# Sheet_1_copy_copy_copy_2022-03-16.net
KiCad netlist of a schematic drawn in Altium Designer
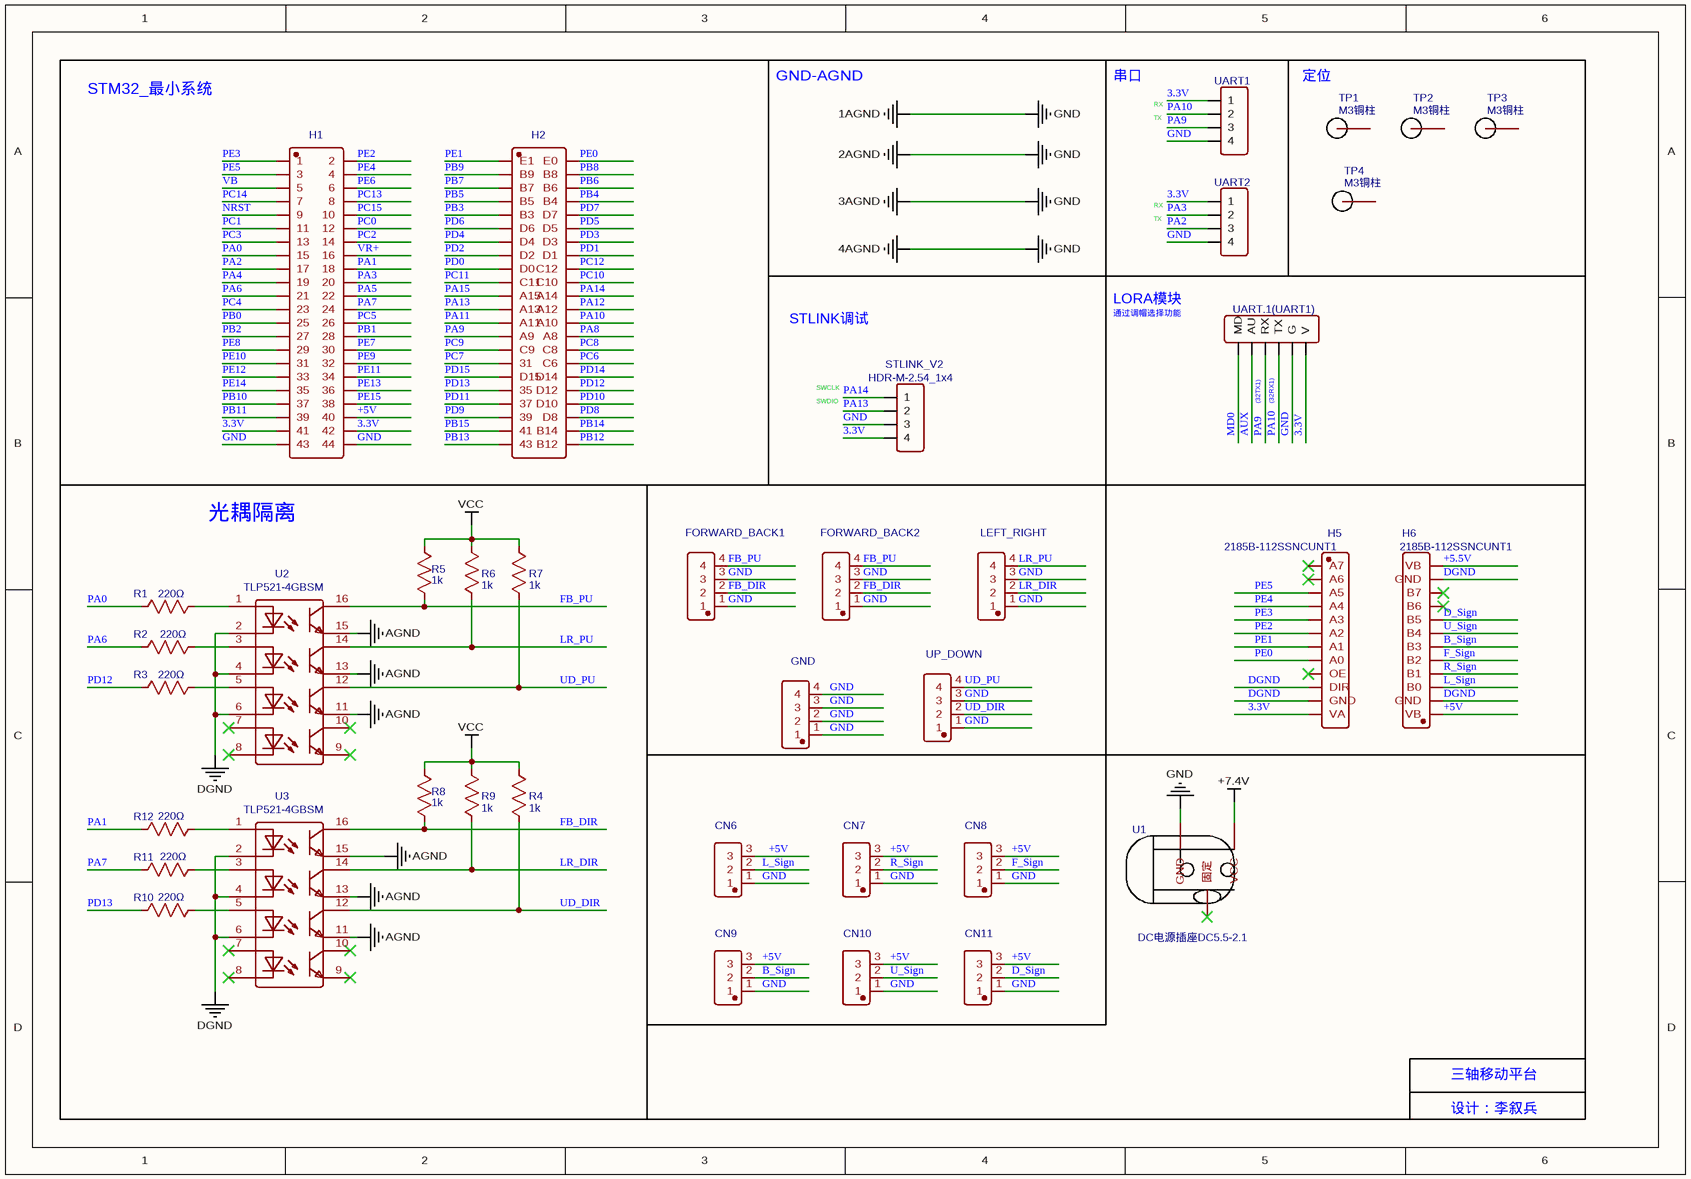
[diagram p0: Sheet_1 copy copy copy_2022-03-16.schdoc]

(export (version "E")
  (design (tool "Eeschema 10.0.6"))
  (components
    (comp (ref "CN6")
      (value "15ETYRC-3.81-03P-14-00AH")
      (footprint "CONN-TH_15ETYRC-3.81-03P-14-00AH")
      (fields (field (name "BOM_SUPPLIER PART") "C2828333") (field (name "CONTRIBUTOR") "LCSC"))
      (libsource (lib "altium-import") (part "root_2_15ETYRC-3.81-03P-14-00AH_"))
    )
    (comp (ref "CN7")
      (value "15ETYRC-3.81-03P-14-00AH")
      (footprint "CONN-TH_15ETYRC-3.81-03P-14-00AH")
      (fields (field (name "BOM_SUPPLIER PART") "C2828333") (field (name "CONTRIBUTOR") "LCSC"))
      (libsource (lib "altium-import") (part "root_2_15ETYRC-3.81-03P-14-00AH_"))
    )
    (comp (ref "CN8")
      (value "15ETYRC-3.81-03P-14-00AH")
      (footprint "CONN-TH_15ETYRC-3.81-03P-14-00AH")
      (fields (field (name "BOM_SUPPLIER PART") "C2828333") (field (name "CONTRIBUTOR") "LCSC"))
      (libsource (lib "altium-import") (part "root_2_15ETYRC-3.81-03P-14-00AH_"))
    )
    (comp (ref "CN9")
      (value "15ETYRC-3.81-03P-14-00AH")
      (footprint "CONN-TH_15ETYRC-3.81-03P-14-00AH")
      (fields (field (name "BOM_SUPPLIER PART") "C2828333") (field (name "CONTRIBUTOR") "LCSC"))
      (libsource (lib "altium-import") (part "root_2_15ETYRC-3.81-03P-14-00AH_"))
    )
    (comp (ref "CN10")
      (value "15ETYRC-3.81-03P-14-00AH")
      (footprint "CONN-TH_15ETYRC-3.81-03P-14-00AH")
      (fields (field (name "BOM_SUPPLIER PART") "C2828333") (field (name "CONTRIBUTOR") "LCSC"))
      (libsource (lib "altium-import") (part "root_2_15ETYRC-3.81-03P-14-00AH_"))
    )
    (comp (ref "CN11")
      (value "15ETYRC-3.81-03P-14-00AH")
      (footprint "CONN-TH_15ETYRC-3.81-03P-14-00AH")
      (fields (field (name "BOM_SUPPLIER PART") "C2828333") (field (name "CONTRIBUTOR") "LCSC"))
      (libsource (lib "altium-import") (part "root_2_15ETYRC-3.81-03P-14-00AH_"))
    )
    (comp (ref "FORWARD_BACK1")
      (value "15ETYRC-3.81-04P-14-00AH")
      (footprint "CONN-TH_15ETYRC-3.81-04P-14-00AH")
      (fields (field (name "BOM_SUPPLIER PART") "C2828334") (field (name "CONTRIBUTOR") "LCSC"))
      (libsource (lib "altium-import") (part "root_2_15ETYRC-3.81-04P-14-00AH_"))
    )
    (comp (ref "FORWARD_BACK2")
      (value "15ETYRC-3.81-04P-14-00AH")
      (footprint "CONN-TH_15ETYRC-3.81-04P-14-00AH")
      (fields (field (name "BOM_SUPPLIER PART") "C2828334") (field (name "CONTRIBUTOR") "LCSC"))
      (libsource (lib "altium-import") (part "root_2_15ETYRC-3.81-04P-14-00AH_"))
    )
    (comp (ref "GND")
      (value "15ETYRC-3.81-04P-14-00AH")
      (footprint "CONN-TH_15ETYRC-3.81-04P-14-00AH")
      (fields (field (name "BOM_SUPPLIER PART") "C2828334") (field (name "CONTRIBUTOR") "LCSC"))
      (libsource (lib "altium-import") (part "root_2_15ETYRC-3.81-04P-14-00AH_"))
    )
    (comp (ref "H1")
      (value "X5521FV-2X22C70D30-1000")
      (footprint "HDR-TH_44P-P2.54-V-F-R2-C22-S2.54")
      (fields
        (field (name "BOM_SUPPLIER PART") "C2682209")
        (field (name "BOM_MANUFACTURER PART") "X5521FV-2x22C70D30-1000")
        (field (name "CONTRIBUTOR") "LCSC")
      )
      (libsource (lib "altium-import") (part "root_0_X5521FV-2X22C70D30-1000_"))
    )
    (comp (ref "H2")
      (value "从5")
      (footprint "HDR-TH_44P-P2.54-V-F-R2-C22-S2.54")
      (fields
        (field (name "BOM_SUPPLIER PART") "C2682209")
        (field (name "BOM_MANUFACTURER PART") "X5521FV-2x22C70D30-1000")
        (field (name "CONTRIBUTOR") "LCSC")
      )
      (libsource (lib "altium-import") (part "root_0_从5_"))
    )
    (comp (ref "H5")
      (value "2185B-112SSNCUNT1")
      (footprint "HDR-TH_12P-P2.54-V-F")
      (fields (field (name "BOM_SUPPLIER PART") "C721800") (field (name "CONTRIBUTOR") "LCSC"))
      (libsource (lib "altium-import") (part "root_0_2185B-112SSNCUNT1_"))
    )
    (comp (ref "H6")
      (value "2185B-112SSNCUNT1")
      (footprint "HDR-TH_12P-P2.54-V-F")
      (fields (field (name "BOM_SUPPLIER PART") "C721800") (field (name "CONTRIBUTOR") "LCSC"))
      (libsource (lib "altium-import") (part "root_2_2185B-112SSNCUNT1_"))
    )
    (comp (ref "LEFT_RIGHT")
      (value "15ETYRC-3.81-04P-14-00AH")
      (footprint "CONN-TH_15ETYRC-3.81-04P-14-00AH")
      (fields (field (name "BOM_SUPPLIER PART") "C2828334") (field (name "CONTRIBUTOR") "LCSC"))
      (libsource (lib "altium-import") (part "root_2_15ETYRC-3.81-04P-14-00AH_"))
    )
    (comp (ref "R1")
      (value "220Ω")
      (footprint "R0603")
      (fields (field (name "CONTRIBUTOR") "LCEDA_Lib"))
      (libsource (lib "altium-import") (part "root_0_220Ω_"))
    )
    (comp (ref "R2")
      (value "220Ω")
      (footprint "R0603")
      (fields (field (name "CONTRIBUTOR") "LCEDA_Lib"))
      (libsource (lib "altium-import") (part "root_0_220Ω_"))
    )
    (comp (ref "R3")
      (value "220Ω")
      (footprint "R0603")
      (fields (field (name "CONTRIBUTOR") "LCEDA_Lib"))
      (libsource (lib "altium-import") (part "root_0_220Ω_"))
    )
    (comp (ref "R4")
      (value "1k")
      (footprint "R0603")
      (fields (field (name "CONTRIBUTOR") "LCEDA_Lib"))
      (libsource (lib "altium-import") (part "root_1_1k_"))
    )
    (comp (ref "R5")
      (value "1k")
      (footprint "R0603")
      (fields (field (name "CONTRIBUTOR") "LCEDA_Lib"))
      (libsource (lib "altium-import") (part "root_1_1k_"))
    )
    (comp (ref "R6")
      (value "1k")
      (footprint "R0603")
      (fields (field (name "CONTRIBUTOR") "LCEDA_Lib"))
      (libsource (lib "altium-import") (part "root_3_1k_"))
    )
    (comp (ref "R7")
      (value "1k")
      (footprint "R0603")
      (fields (field (name "CONTRIBUTOR") "LCEDA_Lib"))
      (libsource (lib "altium-import") (part "root_1_1k_"))
    )
    (comp (ref "R8")
      (value "1k")
      (footprint "R0603")
      (fields (field (name "CONTRIBUTOR") "LCEDA_Lib"))
      (libsource (lib "altium-import") (part "root_1_1k_"))
    )
    (comp (ref "R9")
      (value "1k")
      (footprint "R0603")
      (fields (field (name "CONTRIBUTOR") "LCEDA_Lib"))
      (libsource (lib "altium-import") (part "root_3_1k_"))
    )
    (comp (ref "R10")
      (value "220Ω")
      (footprint "R0603")
      (fields (field (name "CONTRIBUTOR") "LCEDA_Lib"))
      (libsource (lib "altium-import") (part "root_0_220Ω_"))
    )
    (comp (ref "R11")
      (value "220Ω")
      (footprint "R0603")
      (fields (field (name "CONTRIBUTOR") "LCEDA_Lib"))
      (libsource (lib "altium-import") (part "root_0_220Ω_"))
    )
    (comp (ref "R12")
      (value "220Ω")
      (footprint "R0603")
      (fields (field (name "CONTRIBUTOR") "LCEDA_Lib"))
      (libsource (lib "altium-import") (part "root_0_220Ω_"))
    )
    (comp (ref "STLINK_V2")
      (value "HDR-M-2.54_1x4")
      (footprint "HDR-M-2.54_1X4")
      (fields (field (name "BOM_SUPPLIER PART") "C124378") (field (name "CONTRIBUTOR") "LCEDA_Lib"))
      (libsource (lib "altium-import") (part "root_0_HDR-M-2.54_1x4_"))
    )
    (comp (ref "TP1")
      (value "M3铜柱")
      (footprint "M3铜柱")
      (fields (field (name "CONTRIBUTOR") "xzxzhao"))
      (libsource (lib "altium-import") (part "root_0_M3铜柱_"))
    )
    (comp (ref "TP2")
      (value "M3铜柱")
      (footprint "M3铜柱")
      (fields (field (name "CONTRIBUTOR") "xzxzhao"))
      (libsource (lib "altium-import") (part "root_0_M3铜柱_"))
    )
    (comp (ref "TP3")
      (value "M3铜柱")
      (footprint "M3铜柱")
      (fields (field (name "CONTRIBUTOR") "xzxzhao"))
      (libsource (lib "altium-import") (part "root_0_M3铜柱_"))
    )
    (comp (ref "TP4")
      (value "M3铜柱")
      (footprint "M3铜柱")
      (fields (field (name "CONTRIBUTOR") "xzxzhao"))
      (libsource (lib "altium-import") (part "root_0_M3铜柱_"))
    )
    (comp (ref "U1")
      (value "DC电源插座DC5.5-2.1")
      (footprint "DC电源插座5.5-2.1")
      (fields (field (name "CONTRIBUTOR") "Ros智能车"))
      (libsource (lib "altium-import") (part "root_0_DC电源插座DC5.5-2.1_"))
    )
    (comp (ref "U2")
      (value "TLP521-4GBSM")
      (footprint "OPTO-SMD-16_L20.0-W6.5-P2.54-LS10.2-BL")
      (fields (field (name "BOM_SUPPLIER PART") "C191332") (field (name "CONTRIBUTOR") "LCSC"))
      (libsource (lib "altium-import") (part "root_0_TLP521-4GBSM_"))
    )
    (comp (ref "U3")
      (value "TLP521-4GBSM")
      (footprint "OPTO-SMD-16_L20.0-W6.5-P2.54-LS10.2-BL")
      (fields (field (name "BOM_SUPPLIER PART") "C191332") (field (name "CONTRIBUTOR") "LCSC"))
      (libsource (lib "altium-import") (part "root_0_TLP521-4GBSM_"))
    )
    (comp (ref "UART.1(UART1)")
      (value "HDR-F-2.54_1x6")
      (footprint "HDR-F-2.54_1X6")
      (fields (field (name "BOM_SUPPLIER PART") "C40877") (field (name "CONTRIBUTOR") "LCEDA_Lib"))
      (libsource (lib "altium-import") (part "root_1_HDR-F-2.54_1x6_"))
    )
    (comp (ref "UART1")
      (value "HDR-M-2.54_1x4")
      (footprint "HDR-M-2.54_1X4")
      (fields (field (name "BOM_SUPPLIER PART") "C124378") (field (name "CONTRIBUTOR") "LCEDA_Lib"))
      (libsource (lib "altium-import") (part "root_0_HDR-M-2.54_1x4_"))
    )
    (comp (ref "UART2")
      (value "HDR-M-2.54_1x4")
      (footprint "HDR-M-2.54_1X4")
      (fields (field (name "BOM_SUPPLIER PART") "C124378") (field (name "CONTRIBUTOR") "LCEDA_Lib"))
      (libsource (lib "altium-import") (part "root_0_HDR-M-2.54_1x4_"))
    )
    (comp (ref "UP_DOWN")
      (value "15ETYRC-3.81-04P-14-00AH")
      (footprint "CONN-TH_15ETYRC-3.81-04P-14-00AH")
      (fields (field (name "BOM_SUPPLIER PART") "C2828334") (field (name "CONTRIBUTOR") "LCSC"))
      (libsource (lib "altium-import") (part "root_2_15ETYRC-3.81-04P-14-00AH_"))
    )
  )
  (nets
    (net (code "1") (name "+7.4V") (class "Default")
      (node (ref "U1") (pin "1") (pinfunction "VCC_1") (pintype "passive"))
    )
    (net (code "2") (name "/+5.5V") (class "Default")
      (node (ref "H6") (pin "12") (pinfunction "VB_12") (pintype "passive"))
    )
    (net (code "3") (name "/+5V") (class "Default")
      (node (ref "CN10") (pin "3") (pinfunction "3_3") (pintype "passive"))
      (node (ref "CN11") (pin "3") (pinfunction "3_3") (pintype "passive"))
      (node (ref "CN6") (pin "3") (pinfunction "3_3") (pintype "passive"))
      (node (ref "CN7") (pin "3") (pinfunction "3_3") (pintype "passive"))
      (node (ref "CN8") (pin "3") (pinfunction "3_3") (pintype "passive"))
      (node (ref "CN9") (pin "3") (pinfunction "3_3") (pintype "passive"))
      (node (ref "H1") (pin "40") (pinfunction "40_40") (pintype "passive"))
      (node (ref "H6") (pin "1") (pinfunction "VB_1") (pintype "passive"))
    )
    (net (code "4") (name "/3.3V") (class "Default")
      (node (ref "H1") (pin "41") (pinfunction "41_41") (pintype "passive"))
      (node (ref "H1") (pin "42") (pinfunction "42_42") (pintype "passive"))
      (node (ref "H5") (pin "12") (pinfunction "VA_12") (pintype "passive"))
      (node (ref "STLINK_V2") (pin "4") (pinfunction "4_4") (pintype "passive"))
      (node (ref "UART.1(UART1)") (pin "6") (pinfunction "V_6") (pintype "passive"))
      (node (ref "UART1") (pin "1") (pinfunction "1_1") (pintype "passive"))
      (node (ref "UART2") (pin "1") (pinfunction "1_1") (pintype "passive"))
    )
    (net (code "5") (name "/AUX") (class "Default")
      (node (ref "UART.1(UART1)") (pin "2") (pinfunction "AU_2") (pintype "passive"))
    )
    (net (code "6") (name "/B_Sign") (class "Default")
      (node (ref "CN9") (pin "2") (pinfunction "2_2") (pintype "passive"))
      (node (ref "H6") (pin "6") (pinfunction "B3_6") (pintype "passive"))
    )
    (net (code "7") (name "/D_Sign") (class "Default")
      (node (ref "CN11") (pin "2") (pinfunction "2_2") (pintype "passive"))
      (node (ref "H6") (pin "8") (pinfunction "B5_8") (pintype "passive"))
    )
    (net (code "8") (name "/FB_DIR") (class "Default")
      (node (ref "FORWARD_BACK1") (pin "2") (pinfunction "2_2") (pintype "passive"))
      (node (ref "FORWARD_BACK2") (pin "2") (pinfunction "2_2") (pintype "passive"))
      (node (ref "R8") (pin "1") (pinfunction "1_1") (pintype "passive"))
      (node (ref "U3") (pin "16") (pinfunction "COL_16") (pintype "passive"))
    )
    (net (code "9") (name "/FB_PU") (class "Default")
      (node (ref "FORWARD_BACK1") (pin "4") (pinfunction "4_4") (pintype "passive"))
      (node (ref "FORWARD_BACK2") (pin "4") (pinfunction "4_4") (pintype "passive"))
      (node (ref "R5") (pin "1") (pinfunction "1_1") (pintype "passive"))
      (node (ref "U2") (pin "16") (pinfunction "COL_16") (pintype "passive"))
    )
    (net (code "10") (name "/F_Sign") (class "Default")
      (node (ref "CN8") (pin "2") (pinfunction "2_2") (pintype "passive"))
      (node (ref "H6") (pin "5") (pinfunction "B2_5") (pintype "passive"))
    )
    (net (code "11") (name "/LR_DIR") (class "Default")
      (node (ref "LEFT_RIGHT") (pin "2") (pinfunction "2_2") (pintype "passive"))
      (node (ref "R9") (pin "2") (pinfunction "2_2") (pintype "passive"))
      (node (ref "U3") (pin "14") (pinfunction "COL_14") (pintype "passive"))
    )
    (net (code "12") (name "/LR_PU") (class "Default")
      (node (ref "LEFT_RIGHT") (pin "4") (pinfunction "4_4") (pintype "passive"))
      (node (ref "R6") (pin "2") (pinfunction "2_2") (pintype "passive"))
      (node (ref "U2") (pin "14") (pinfunction "COL_14") (pintype "passive"))
    )
    (net (code "13") (name "/L_Sign") (class "Default")
      (node (ref "CN6") (pin "2") (pinfunction "2_2") (pintype "passive"))
      (node (ref "H6") (pin "3") (pinfunction "B0_3") (pintype "passive"))
    )
    (net (code "14") (name "/MD0") (class "Default")
      (node (ref "UART.1(UART1)") (pin "1") (pinfunction "MD_1") (pintype "passive"))
    )
    (net (code "15") (name "/NRST") (class "Default")
      (node (ref "H1") (pin "9") (pinfunction "9_9") (pintype "passive"))
    )
    (net (code "16") (name "/PA0") (class "Default")
      (node (ref "H1") (pin "15") (pinfunction "15_15") (pintype "passive"))
      (node (ref "R1") (pin "1") (pinfunction "1_1") (pintype "passive"))
    )
    (net (code "17") (name "/PA1") (class "Default")
      (node (ref "H1") (pin "18") (pinfunction "18_18") (pintype "passive"))
      (node (ref "R12") (pin "1") (pinfunction "1_1") (pintype "passive"))
    )
    (net (code "18") (name "/PA2") (class "Default")
      (node (ref "H1") (pin "17") (pinfunction "17_17") (pintype "passive"))
      (node (ref "UART2") (pin "3") (pinfunction "3_3") (pintype "passive"))
    )
    (net (code "19") (name "/PA3") (class "Default")
      (node (ref "H1") (pin "20") (pinfunction "20_20") (pintype "passive"))
      (node (ref "UART2") (pin "2") (pinfunction "2_2") (pintype "passive"))
    )
    (net (code "20") (name "/PA4") (class "Default")
      (node (ref "H1") (pin "19") (pinfunction "19_19") (pintype "passive"))
    )
    (net (code "21") (name "/PA5") (class "Default")
      (node (ref "H1") (pin "22") (pinfunction "22_22") (pintype "passive"))
    )
    (net (code "22") (name "/PA6") (class "Default")
      (node (ref "H1") (pin "21") (pinfunction "21_21") (pintype "passive"))
      (node (ref "R2") (pin "1") (pinfunction "1_1") (pintype "passive"))
    )
    (net (code "23") (name "/PA7") (class "Default")
      (node (ref "H1") (pin "24") (pinfunction "24_24") (pintype "passive"))
      (node (ref "R11") (pin "1") (pinfunction "1_1") (pintype "passive"))
    )
    (net (code "24") (name "/PA8") (class "Default")
      (node (ref "H2") (pin "28") (pinfunction "A8_28") (pintype "passive"))
    )
    (net (code "25") (name "/PA9") (class "Default")
      (node (ref "H2") (pin "27") (pinfunction "A9_27") (pintype "passive"))
      (node (ref "UART.1(UART1)") (pin "3") (pinfunction "RX_3") (pintype "passive"))
      (node (ref "UART1") (pin "3") (pinfunction "3_3") (pintype "passive"))
    )
    (net (code "26") (name "/PA10") (class "Default")
      (node (ref "H2") (pin "26") (pinfunction "A10_26") (pintype "passive"))
      (node (ref "UART.1(UART1)") (pin "4") (pinfunction "TX_4") (pintype "passive"))
      (node (ref "UART1") (pin "2") (pinfunction "2_2") (pintype "passive"))
    )
    (net (code "27") (name "/PA11") (class "Default")
      (node (ref "H2") (pin "25") (pinfunction "A11_25") (pintype "passive"))
    )
    (net (code "28") (name "/PA12") (class "Default")
      (node (ref "H2") (pin "24") (pinfunction "A12_24") (pintype "passive"))
    )
    (net (code "29") (name "/PA13") (class "Default")
      (node (ref "H2") (pin "23") (pinfunction "A13_23") (pintype "passive"))
      (node (ref "STLINK_V2") (pin "2") (pinfunction "2_2") (pintype "passive"))
    )
    (net (code "30") (name "/PA14") (class "Default")
      (node (ref "H2") (pin "22") (pinfunction "A14_22") (pintype "passive"))
      (node (ref "STLINK_V2") (pin "1") (pinfunction "1_1") (pintype "passive"))
    )
    (net (code "31") (name "/PA15") (class "Default")
      (node (ref "H2") (pin "21") (pinfunction "A15_21") (pintype "passive"))
    )
    (net (code "32") (name "/PB0") (class "Default")
      (node (ref "H1") (pin "25") (pinfunction "25_25") (pintype "passive"))
    )
    (net (code "33") (name "/PB1") (class "Default")
      (node (ref "H1") (pin "28") (pinfunction "28_28") (pintype "passive"))
    )
    (net (code "34") (name "/PB2") (class "Default")
      (node (ref "H1") (pin "27") (pinfunction "27_27") (pintype "passive"))
    )
    (net (code "35") (name "/PB3") (class "Default")
      (node (ref "H2") (pin "9") (pinfunction "B3_9") (pintype "passive"))
    )
    (net (code "36") (name "/PB4") (class "Default")
      (node (ref "H2") (pin "8") (pinfunction "B4_8") (pintype "passive"))
    )
    (net (code "37") (name "/PB5") (class "Default")
      (node (ref "H2") (pin "7") (pinfunction "B5_7") (pintype "passive"))
    )
    (net (code "38") (name "/PB6") (class "Default")
      (node (ref "H2") (pin "6") (pinfunction "B6_6") (pintype "passive"))
    )
    (net (code "39") (name "/PB7") (class "Default")
      (node (ref "H2") (pin "5") (pinfunction "B7_5") (pintype "passive"))
    )
    (net (code "40") (name "/PB8") (class "Default")
      (node (ref "H2") (pin "4") (pinfunction "B8_4") (pintype "passive"))
    )
    (net (code "41") (name "/PB9") (class "Default")
      (node (ref "H2") (pin "3") (pinfunction "B9_3") (pintype "passive"))
    )
    (net (code "42") (name "/PB10") (class "Default")
      (node (ref "H1") (pin "37") (pinfunction "37_37") (pintype "passive"))
    )
    (net (code "43") (name "/PB11") (class "Default")
      (node (ref "H1") (pin "39") (pinfunction "39_39") (pintype "passive"))
    )
    (net (code "44") (name "/PB12") (class "Default")
      (node (ref "H2") (pin "44") (pinfunction "B12_44") (pintype "passive"))
    )
    (net (code "45") (name "/PB13") (class "Default")
      (node (ref "H2") (pin "43") (pinfunction "43_43") (pintype "passive"))
    )
    (net (code "46") (name "/PB14") (class "Default")
      (node (ref "H2") (pin "42") (pinfunction "B14_42") (pintype "passive"))
    )
    (net (code "47") (name "/PB15") (class "Default")
      (node (ref "H2") (pin "41") (pinfunction "41_41") (pintype "passive"))
    )
    (net (code "48") (name "/PC0") (class "Default")
      (node (ref "H1") (pin "12") (pinfunction "12_12") (pintype "passive"))
    )
    (net (code "49") (name "/PC1") (class "Default")
      (node (ref "H1") (pin "11") (pinfunction "11_11") (pintype "passive"))
    )
    (net (code "50") (name "/PC2") (class "Default")
      (node (ref "H1") (pin "14") (pinfunction "14_14") (pintype "passive"))
    )
    (net (code "51") (name "/PC3") (class "Default")
      (node (ref "H1") (pin "13") (pinfunction "13_13") (pintype "passive"))
    )
    (net (code "52") (name "/PC4") (class "Default")
      (node (ref "H1") (pin "23") (pinfunction "23_23") (pintype "passive"))
    )
    (net (code "53") (name "/PC5") (class "Default")
      (node (ref "H1") (pin "26") (pinfunction "26_26") (pintype "passive"))
    )
    (net (code "54") (name "/PC6") (class "Default")
      (node (ref "H2") (pin "32") (pinfunction "C6_32") (pintype "passive"))
    )
    (net (code "55") (name "/PC7") (class "Default")
      (node (ref "H2") (pin "31") (pinfunction "31_31") (pintype "passive"))
    )
    (net (code "56") (name "/PC8") (class "Default")
      (node (ref "H2") (pin "30") (pinfunction "C8_30") (pintype "passive"))
    )
    (net (code "57") (name "/PC9") (class "Default")
      (node (ref "H2") (pin "29") (pinfunction "C9_29") (pintype "passive"))
    )
    (net (code "58") (name "/PC10") (class "Default")
      (node (ref "H2") (pin "20") (pinfunction "C10_20") (pintype "passive"))
    )
    (net (code "59") (name "/PC11") (class "Default")
      (node (ref "H2") (pin "19") (pinfunction "C11_19") (pintype "passive"))
    )
    (net (code "60") (name "/PC12") (class "Default")
      (node (ref "H2") (pin "18") (pinfunction "C12_18") (pintype "passive"))
    )
    (net (code "61") (name "/PC13") (class "Default")
      (node (ref "H1") (pin "8") (pinfunction "8_8") (pintype "passive"))
    )
    (net (code "62") (name "/PC14") (class "Default")
      (node (ref "H1") (pin "7") (pinfunction "7_7") (pintype "passive"))
    )
    (net (code "63") (name "/PC15") (class "Default")
      (node (ref "H1") (pin "10") (pinfunction "10_10") (pintype "passive"))
    )
    (net (code "64") (name "/PD0") (class "Default")
      (node (ref "H2") (pin "17") (pinfunction "D0_17") (pintype "passive"))
    )
    (net (code "65") (name "/PD1") (class "Default")
      (node (ref "H2") (pin "16") (pinfunction "D1_16") (pintype "passive"))
    )
    (net (code "66") (name "/PD2") (class "Default")
      (node (ref "H2") (pin "15") (pinfunction "D2_15") (pintype "passive"))
    )
    (net (code "67") (name "/PD3") (class "Default")
      (node (ref "H2") (pin "14") (pinfunction "D3_14") (pintype "passive"))
    )
    (net (code "68") (name "/PD4") (class "Default")
      (node (ref "H2") (pin "13") (pinfunction "D4_13") (pintype "passive"))
    )
    (net (code "69") (name "/PD5") (class "Default")
      (node (ref "H2") (pin "12") (pinfunction "D5_12") (pintype "passive"))
    )
    (net (code "70") (name "/PD6") (class "Default")
      (node (ref "H2") (pin "11") (pinfunction "D6_11") (pintype "passive"))
    )
    (net (code "71") (name "/PD7") (class "Default")
      (node (ref "H2") (pin "10") (pinfunction "D7_10") (pintype "passive"))
    )
    (net (code "72") (name "/PD8") (class "Default")
      (node (ref "H2") (pin "40") (pinfunction "D8_40") (pintype "passive"))
    )
    (net (code "73") (name "/PD9") (class "Default")
      (node (ref "H2") (pin "39") (pinfunction "39_39") (pintype "passive"))
    )
    (net (code "74") (name "/PD10") (class "Default")
      (node (ref "H2") (pin "38") (pinfunction "D10_38") (pintype "passive"))
    )
    (net (code "75") (name "/PD11") (class "Default")
      (node (ref "H2") (pin "37") (pinfunction "37_37") (pintype "passive"))
    )
    (net (code "76") (name "/PD12") (class "Default")
      (node (ref "H2") (pin "36") (pinfunction "D12_36") (pintype "passive"))
      (node (ref "R3") (pin "1") (pinfunction "1_1") (pintype "passive"))
    )
    (net (code "77") (name "/PD13") (class "Default")
      (node (ref "H2") (pin "35") (pinfunction "35_35") (pintype "passive"))
      (node (ref "R10") (pin "1") (pinfunction "1_1") (pintype "passive"))
    )
    (net (code "78") (name "/PD14") (class "Default")
      (node (ref "H2") (pin "34") (pinfunction "D14_34") (pintype "passive"))
    )
    (net (code "79") (name "/PD15") (class "Default")
      (node (ref "H2") (pin "33") (pinfunction "D15_33") (pintype "passive"))
    )
    (net (code "80") (name "/PE0") (class "Default")
      (node (ref "H2") (pin "2") (pinfunction "E0_2") (pintype "passive"))
      (node (ref "H5") (pin "8") (pinfunction "A0_8") (pintype "passive"))
    )
    (net (code "81") (name "/PE1") (class "Default")
      (node (ref "H2") (pin "1") (pinfunction "E1_1") (pintype "passive"))
      (node (ref "H5") (pin "7") (pinfunction "A1_7") (pintype "passive"))
    )
    (net (code "82") (name "/PE2") (class "Default")
      (node (ref "H1") (pin "2") (pinfunction "2_2") (pintype "passive"))
      (node (ref "H5") (pin "6") (pinfunction "A2_6") (pintype "passive"))
    )
    (net (code "83") (name "/PE3") (class "Default")
      (node (ref "H1") (pin "1") (pinfunction "1_1") (pintype "passive"))
      (node (ref "H5") (pin "5") (pinfunction "A3_5") (pintype "passive"))
    )
    (net (code "84") (name "/PE4") (class "Default")
      (node (ref "H1") (pin "4") (pinfunction "4_4") (pintype "passive"))
      (node (ref "H5") (pin "4") (pinfunction "A4_4") (pintype "passive"))
    )
    (net (code "85") (name "/PE5") (class "Default")
      (node (ref "H1") (pin "3") (pinfunction "3_3") (pintype "passive"))
      (node (ref "H5") (pin "3") (pinfunction "A5_3") (pintype "passive"))
    )
    (net (code "86") (name "/PE6") (class "Default")
      (node (ref "H1") (pin "6") (pinfunction "6_6") (pintype "passive"))
    )
    (net (code "87") (name "/PE7") (class "Default")
      (node (ref "H1") (pin "30") (pinfunction "30_30") (pintype "passive"))
    )
    (net (code "88") (name "/PE8") (class "Default")
      (node (ref "H1") (pin "29") (pinfunction "29_29") (pintype "passive"))
    )
    (net (code "89") (name "/PE9") (class "Default")
      (node (ref "H1") (pin "32") (pinfunction "32_32") (pintype "passive"))
    )
    (net (code "90") (name "/PE10") (class "Default")
      (node (ref "H1") (pin "31") (pinfunction "31_31") (pintype "passive"))
    )
    (net (code "91") (name "/PE11") (class "Default")
      (node (ref "H1") (pin "34") (pinfunction "34_34") (pintype "passive"))
    )
    (net (code "92") (name "/PE12") (class "Default")
      (node (ref "H1") (pin "33") (pinfunction "33_33") (pintype "passive"))
    )
    (net (code "93") (name "/PE13") (class "Default")
      (node (ref "H1") (pin "36") (pinfunction "36_36") (pintype "passive"))
    )
    (net (code "94") (name "/PE14") (class "Default")
      (node (ref "H1") (pin "35") (pinfunction "35_35") (pintype "passive"))
    )
    (net (code "95") (name "/PE15") (class "Default")
      (node (ref "H1") (pin "38") (pinfunction "38_38") (pintype "passive"))
    )
    (net (code "96") (name "/R_Sign") (class "Default")
      (node (ref "CN7") (pin "2") (pinfunction "2_2") (pintype "passive"))
      (node (ref "H6") (pin "4") (pinfunction "B1_4") (pintype "passive"))
    )
    (net (code "97") (name "/UD_DIR") (class "Default")
      (node (ref "R4") (pin "1") (pinfunction "1_1") (pintype "passive"))
      (node (ref "U3") (pin "12") (pinfunction "COL_12") (pintype "passive"))
      (node (ref "UP_DOWN") (pin "2") (pinfunction "2_2") (pintype "passive"))
    )
    (net (code "98") (name "/UD_PU") (class "Default")
      (node (ref "R7") (pin "1") (pinfunction "1_1") (pintype "passive"))
      (node (ref "U2") (pin "12") (pinfunction "COL_12") (pintype "passive"))
      (node (ref "UP_DOWN") (pin "4") (pinfunction "4_4") (pintype "passive"))
    )
    (net (code "99") (name "/U_Sign") (class "Default")
      (node (ref "CN10") (pin "2") (pinfunction "2_2") (pintype "passive"))
      (node (ref "H6") (pin "7") (pinfunction "B4_7") (pintype "passive"))
    )
    (net (code "100") (name "/VB") (class "Default")
      (node (ref "H1") (pin "5") (pinfunction "5_5") (pintype "passive"))
    )
    (net (code "101") (name "/VR+") (class "Default")
      (node (ref "H1") (pin "16") (pinfunction "16_16") (pintype "passive"))
    )
    (net (code "102") (name "1AGND") (class "Default")
      (node (ref "CN10") (pin "1") (pinfunction "1_1") (pintype "passive"))
      (node (ref "CN11") (pin "1") (pinfunction "1_1") (pintype "passive"))
      (node (ref "CN6") (pin "1") (pinfunction "1_1") (pintype "passive"))
      (node (ref "CN7") (pin "1") (pinfunction "1_1") (pintype "passive"))
      (node (ref "CN8") (pin "1") (pinfunction "1_1") (pintype "passive"))
      (node (ref "CN9") (pin "1") (pinfunction "1_1") (pintype "passive"))
      (node (ref "FORWARD_BACK1") (pin "1") (pinfunction "1_1") (pintype "passive"))
      (node (ref "FORWARD_BACK1") (pin "3") (pinfunction "3_3") (pintype "passive"))
      (node (ref "FORWARD_BACK2") (pin "1") (pinfunction "1_1") (pintype "passive"))
      (node (ref "FORWARD_BACK2") (pin "3") (pinfunction "3_3") (pintype "passive"))
      (node (ref "GND") (pin "1") (pinfunction "1_1") (pintype "passive"))
      (node (ref "GND") (pin "2") (pinfunction "2_2") (pintype "passive"))
      (node (ref "GND") (pin "3") (pinfunction "3_3") (pintype "passive"))
      (node (ref "GND") (pin "4") (pinfunction "4_4") (pintype "passive"))
      (node (ref "H1") (pin "43") (pinfunction "43_43") (pintype "passive"))
      (node (ref "H1") (pin "44") (pinfunction "44_44") (pintype "passive"))
      (node (ref "LEFT_RIGHT") (pin "1") (pinfunction "1_1") (pintype "passive"))
      (node (ref "LEFT_RIGHT") (pin "3") (pinfunction "3_3") (pintype "passive"))
      (node (ref "STLINK_V2") (pin "3") (pinfunction "3_3") (pintype "passive"))
      (node (ref "U1") (pin "2") (pinfunction "GND_2") (pintype "passive"))
      (node (ref "UART.1(UART1)") (pin "5") (pinfunction "G_5") (pintype "passive"))
      (node (ref "UART1") (pin "4") (pinfunction "4_4") (pintype "passive"))
      (node (ref "UART2") (pin "4") (pinfunction "4_4") (pintype "passive"))
      (node (ref "UP_DOWN") (pin "1") (pinfunction "1_1") (pintype "passive"))
      (node (ref "UP_DOWN") (pin "3") (pinfunction "3_3") (pintype "passive"))
    )
    (net (code "103") (name "AGND") (class "Default")
      (node (ref "U2") (pin "11") (pinfunction "EM_11") (pintype "passive"))
      (node (ref "U2") (pin "13") (pinfunction "EM_13") (pintype "passive"))
      (node (ref "U2") (pin "15") (pinfunction "EM_15") (pintype "passive"))
      (node (ref "U3") (pin "11") (pinfunction "EM_11") (pintype "passive"))
      (node (ref "U3") (pin "13") (pinfunction "EM_13") (pintype "passive"))
      (node (ref "U3") (pin "15") (pinfunction "EM_15") (pintype "passive"))
    )
    (net (code "104") (name "DGND") (class "Default")
      (node (ref "H5") (pin "10") (pinfunction "DIR_10") (pintype "passive"))
      (node (ref "H5") (pin "11") (pinfunction "GND_11") (pintype "passive"))
      (node (ref "H6") (pin "11") (pinfunction "GND_11") (pintype "passive"))
      (node (ref "H6") (pin "2") (pinfunction "GND_2") (pintype "passive"))
      (node (ref "U2") (pin "2") (pinfunction "CAT_2") (pintype "passive"))
      (node (ref "U2") (pin "4") (pinfunction "CAT_4") (pintype "passive"))
      (node (ref "U2") (pin "6") (pinfunction "CAT_6") (pintype "passive"))
      (node (ref "U3") (pin "2") (pinfunction "CAT_2") (pintype "passive"))
      (node (ref "U3") (pin "4") (pinfunction "CAT_4") (pintype "passive"))
      (node (ref "U3") (pin "6") (pinfunction "CAT_6") (pintype "passive"))
    )
    (net (code "105") (name "Net-(R1-Pad2)") (class "Default")
      (node (ref "R1") (pin "2") (pinfunction "2_2") (pintype "passive"))
      (node (ref "U2") (pin "1") (pinfunction "AN_1") (pintype "passive"))
    )
    (net (code "106") (name "Net-(R2-Pad2)") (class "Default")
      (node (ref "R2") (pin "2") (pinfunction "2_2") (pintype "passive"))
      (node (ref "U2") (pin "3") (pinfunction "AN_3") (pintype "passive"))
    )
    (net (code "107") (name "Net-(R3-Pad2)") (class "Default")
      (node (ref "R3") (pin "2") (pinfunction "2_2") (pintype "passive"))
      (node (ref "U2") (pin "5") (pinfunction "AN_5") (pintype "passive"))
    )
    (net (code "108") (name "Net-(R10-Pad2)") (class "Default")
      (node (ref "R10") (pin "2") (pinfunction "2_2") (pintype "passive"))
      (node (ref "U3") (pin "5") (pinfunction "AN_5") (pintype "passive"))
    )
    (net (code "109") (name "Net-(R11-Pad2)") (class "Default")
      (node (ref "R11") (pin "2") (pinfunction "2_2") (pintype "passive"))
      (node (ref "U3") (pin "3") (pinfunction "AN_3") (pintype "passive"))
    )
    (net (code "110") (name "Net-(R12-Pad2)") (class "Default")
      (node (ref "R12") (pin "2") (pinfunction "2_2") (pintype "passive"))
      (node (ref "U3") (pin "1") (pinfunction "AN_1") (pintype "passive"))
    )
    (net (code "111") (name "VCC") (class "Default")
      (node (ref "R4") (pin "2") (pinfunction "2_2") (pintype "passive"))
      (node (ref "R5") (pin "2") (pinfunction "2_2") (pintype "passive"))
      (node (ref "R6") (pin "1") (pinfunction "1_1") (pintype "passive"))
      (node (ref "R7") (pin "2") (pinfunction "2_2") (pintype "passive"))
      (node (ref "R8") (pin "2") (pinfunction "2_2") (pintype "passive"))
      (node (ref "R9") (pin "1") (pinfunction "1_1") (pintype "passive"))
    )
    (net (code "112") (name "unconnected-(H5-A6-Pad2)") (class "Default")
      (node (ref "H5") (pin "2") (pinfunction "A6_2") (pintype "passive+no_connect"))
    )
    (net (code "113") (name "unconnected-(H5-A7-Pad1)") (class "Default")
      (node (ref "H5") (pin "1") (pinfunction "A7_1") (pintype "passive+no_connect"))
    )
    (net (code "114") (name "unconnected-(H5-OE-Pad9)") (class "Default")
      (node (ref "H5") (pin "9") (pinfunction "OE_9") (pintype "passive+no_connect"))
    )
    (net (code "115") (name "unconnected-(H6-B6-Pad9)") (class "Default")
      (node (ref "H6") (pin "9") (pinfunction "B6_9") (pintype "passive+no_connect"))
    )
    (net (code "116") (name "unconnected-(H6-B7-Pad10)") (class "Default")
      (node (ref "H6") (pin "10") (pinfunction "B7_10") (pintype "passive+no_connect"))
    )
    (net (code "117") (name "unconnected-(TP1-M3-Pad1)") (class "Default")
      (node (ref "TP1") (pin "1") (pinfunction "M3_1") (pintype "passive"))
    )
    (net (code "118") (name "unconnected-(TP2-M3-Pad1)") (class "Default")
      (node (ref "TP2") (pin "1") (pinfunction "M3_1") (pintype "passive"))
    )
    (net (code "119") (name "unconnected-(TP3-M3-Pad1)") (class "Default")
      (node (ref "TP3") (pin "1") (pinfunction "M3_1") (pintype "passive"))
    )
    (net (code "120") (name "unconnected-(TP4-M3-Pad1)") (class "Default")
      (node (ref "TP4") (pin "1") (pinfunction "M3_1") (pintype "passive"))
    )
    (net (code "121") (name "unconnected-(U1-固定-Pad3)") (class "Default")
      (node (ref "U1") (pin "3") (pinfunction "固定_3") (pintype "passive+no_connect"))
    )
    (net (code "122") (name "unconnected-(U2-AN-Pad7)") (class "Default")
      (node (ref "U2") (pin "7") (pinfunction "AN_7") (pintype "passive+no_connect"))
    )
    (net (code "123") (name "unconnected-(U2-CAT-Pad8)") (class "Default")
      (node (ref "U2") (pin "8") (pinfunction "CAT_8") (pintype "passive+no_connect"))
    )
    (net (code "124") (name "unconnected-(U2-COL-Pad10)") (class "Default")
      (node (ref "U2") (pin "10") (pinfunction "COL_10") (pintype "passive+no_connect"))
    )
    (net (code "125") (name "unconnected-(U2-EM-Pad9)") (class "Default")
      (node (ref "U2") (pin "9") (pinfunction "EM_9") (pintype "passive+no_connect"))
    )
    (net (code "126") (name "unconnected-(U3-AN-Pad7)") (class "Default")
      (node (ref "U3") (pin "7") (pinfunction "AN_7") (pintype "passive+no_connect"))
    )
    (net (code "127") (name "unconnected-(U3-CAT-Pad8)") (class "Default")
      (node (ref "U3") (pin "8") (pinfunction "CAT_8") (pintype "passive+no_connect"))
    )
    (net (code "128") (name "unconnected-(U3-COL-Pad10)") (class "Default")
      (node (ref "U3") (pin "10") (pinfunction "COL_10") (pintype "passive+no_connect"))
    )
    (net (code "129") (name "unconnected-(U3-EM-Pad9)") (class "Default")
      (node (ref "U3") (pin "9") (pinfunction "EM_9") (pintype "passive+no_connect"))
    )
  )
)
